# ProPrj___2026-03-26.net
KiCad netlist of a schematic drawn in EasyEDA Pro
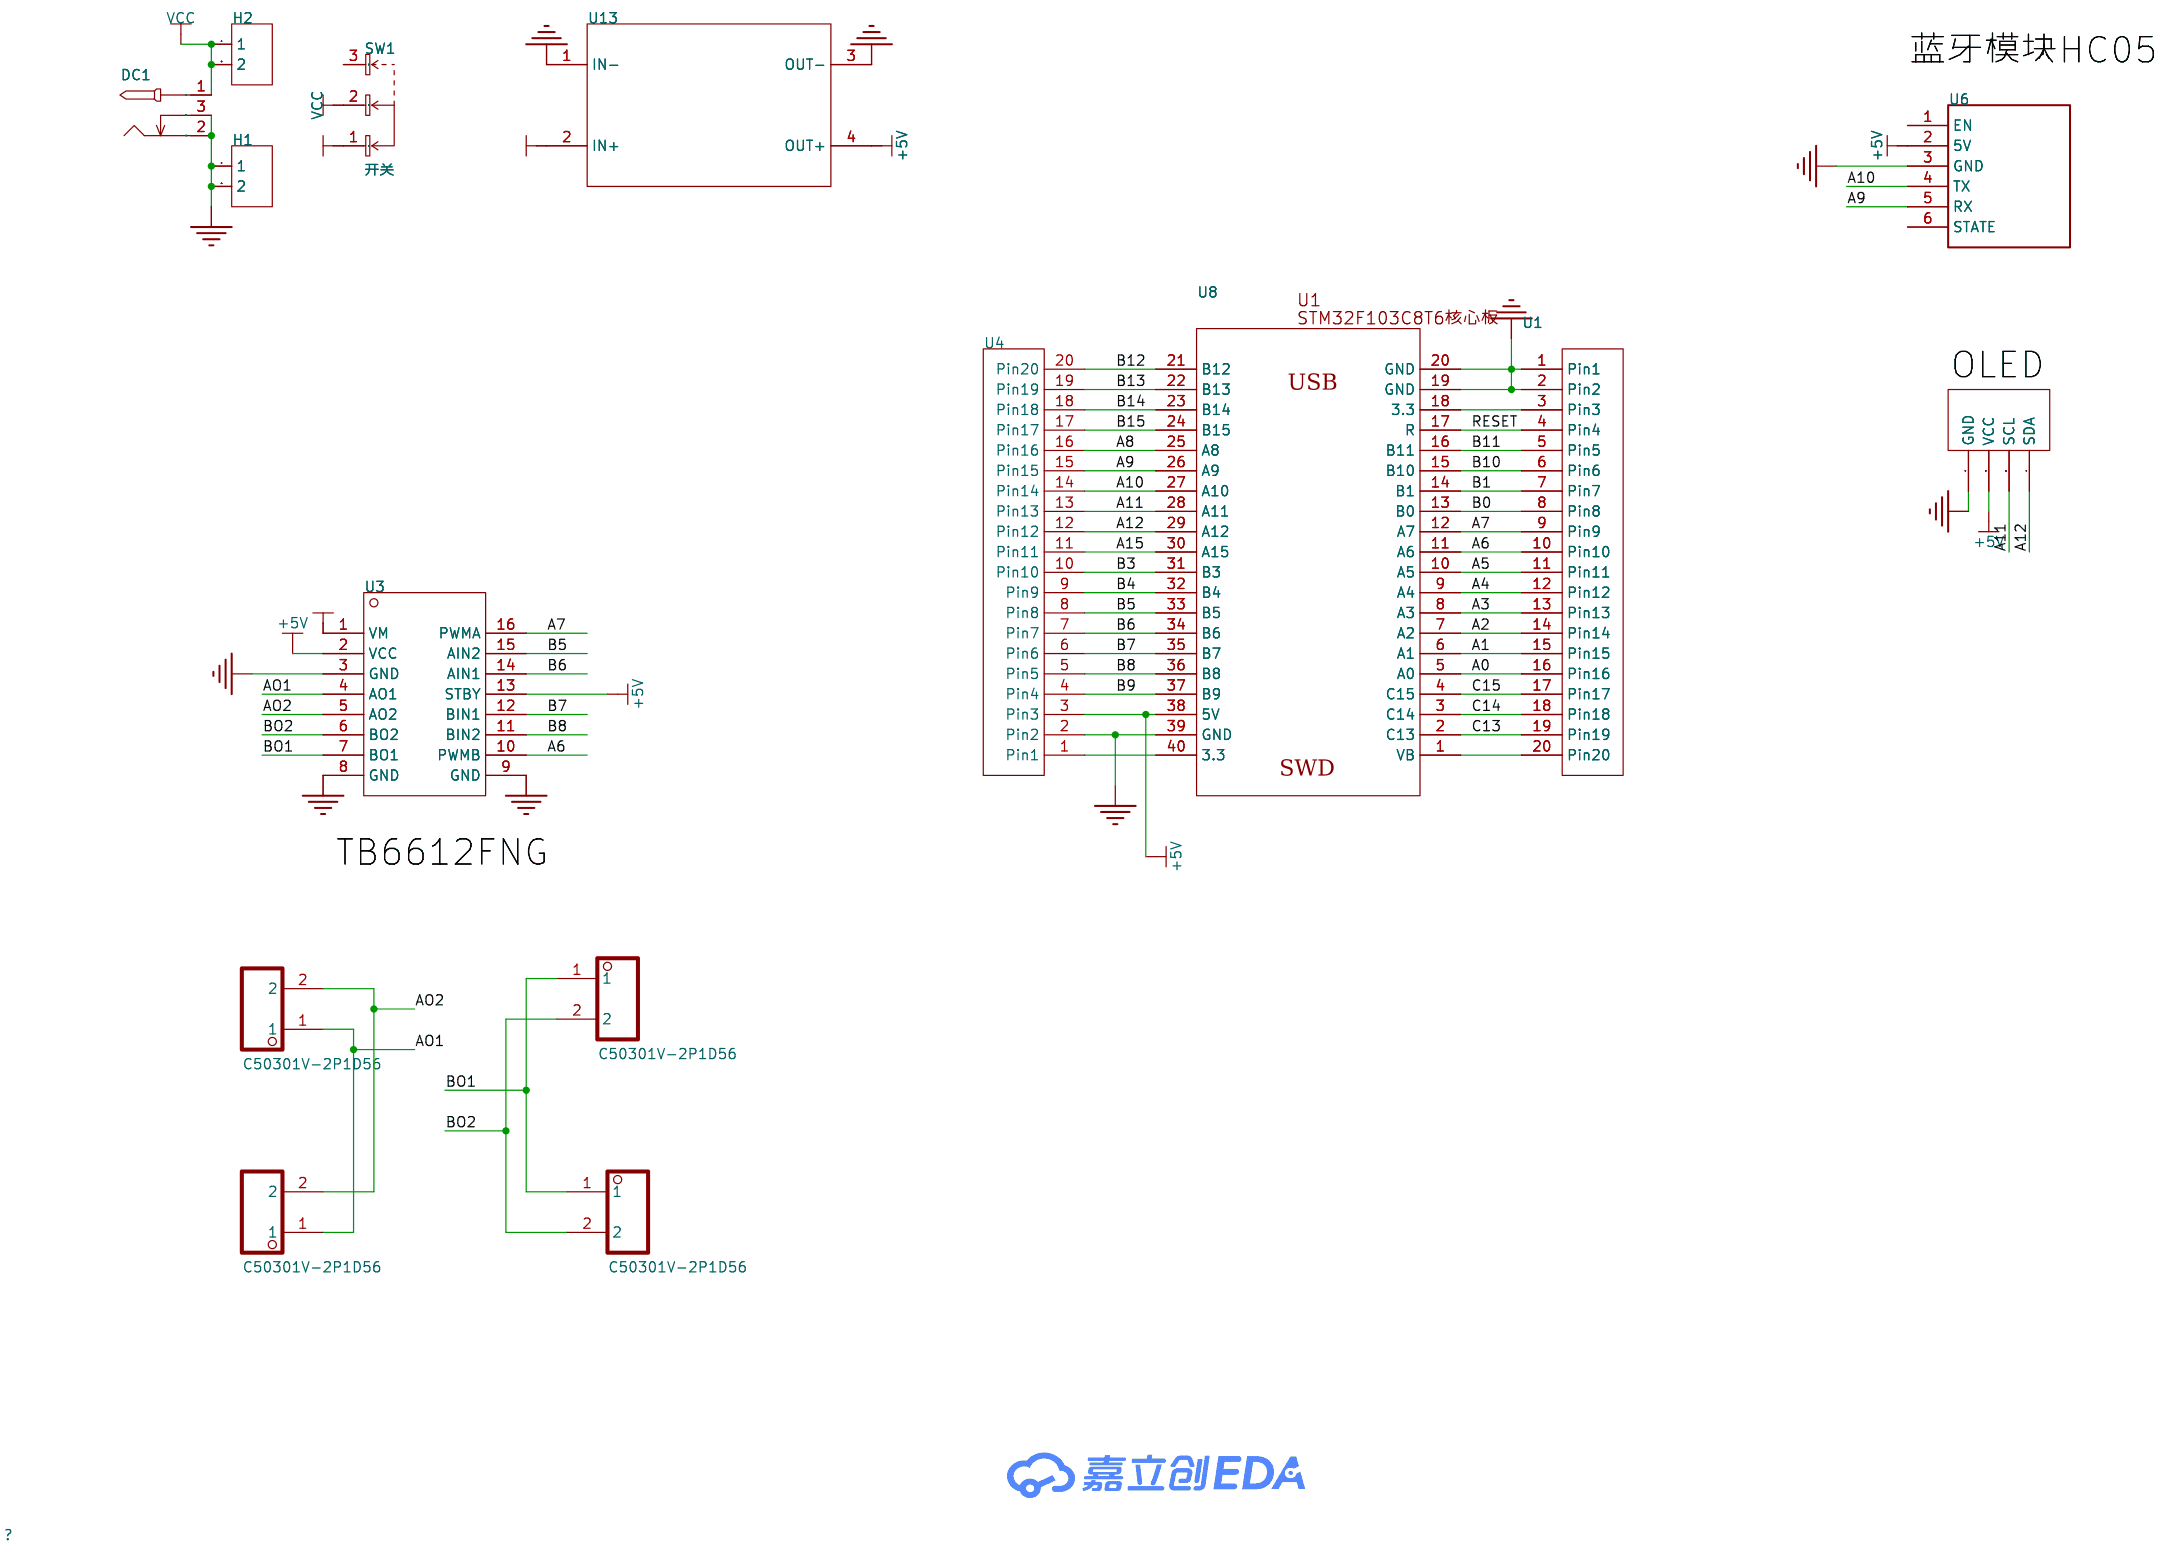
[diagram p0: schematic sheet]

(export (version "E")
  (design (tool "Eeschema 10.0.6"))
  (components
    (comp (ref "DC1")
      (value "~")
      (footprint "easyedapro:DC-005_2.5")
      (libsource (lib "easyedapro") (part "DC-005_2.5"))
    )
    (comp (ref "H1")
      (value "~")
      (footprint "easyedapro:HDR-TH_2P-P2.54-V-F")
      (libsource (lib "easyedapro") (part "Header-Female-2.54_1x2"))
    )
    (comp (ref "H2")
      (value "~")
      (footprint "easyedapro:HDR-TH_2P-P2.54-V-F")
      (libsource (lib "easyedapro") (part "Header-Female-2.54_1x2"))
    )
    (comp (ref "OLED")
      (value "OLED4PIN")
      (footprint "easyedapro:OLED 4PIN")
      (libsource (lib "easyedapro") (part "OLED 4PIN"))
    )
    (comp (ref "SW1")
      (value "开关")
      (footprint "easyedapro:SW-TH_3P-P4.70_L11.1-W12.7")
      (description "电路结构:单刀双掷;安装方式:-;开关颜色:黑色;额定电流:3A;额定电压:250V;工作寿命:1万次;")
      (fields
        (field (name "Manufacturer Part") "SS-12D06L5")
        (field (name "Manufacturer") "XKB Connection(中国星坤)")
      )
      (libsource (lib "easyedapro") (part "SS-12D06L5"))
    )
    (comp (ref "U1") (value "~") (footprint "easyedapro:20p排针") (libsource (lib "easyedapro") (part "20p排针")))
    (comp (ref "U3")
      (value "TB6612FNG")
      (footprint "easyedapro:TB6612")
      (libsource (lib "easyedapro") (part "TB6612"))
    )
    (comp (ref "U4") (value "~") (footprint "easyedapro:20p排针") (libsource (lib "easyedapro") (part "20p排针")))
    (comp (ref "U6")
      (value "蓝牙模块HC05")
      (footprint "easyedapro:HC05")
      (libsource (lib "easyedapro") (part "HC05"))
    )
    (comp (ref "U8")
      (value "~")
      (footprint "easyedapro:STM32F103C8T6核心板")
      (libsource (lib "easyedapro") (part "STM32F103核心板"))
    )
    (comp (ref "U9")
      (value "C50301V-2P1D56")
      (footprint "easyedapro:螺钉式接线端子")
      (description "低价方案")
      (libsource (lib "easyedapro") (part "螺钉式接线端子"))
    )
    (comp (ref "U10")
      (value "C50301V-2P1D56")
      (footprint "easyedapro:螺钉式接线端子")
      (description "低价方案")
      (libsource (lib "easyedapro") (part "螺钉式接线端子"))
    )
    (comp (ref "U11")
      (value "C50301V-2P1D56")
      (footprint "easyedapro:螺钉式接线端子")
      (description "低价方案")
      (libsource (lib "easyedapro") (part "螺钉式接线端子"))
    )
    (comp (ref "U12")
      (value "C50301V-2P1D56")
      (footprint "easyedapro:螺钉式接线端子")
      (description "低价方案")
      (libsource (lib "easyedapro") (part "螺钉式接线端子"))
    )
    (comp (ref "U13")
      (value "~")
      (footprint "easyedapro:MP1584en")
      (libsource (lib "easyedapro") (part "MP1584en"))
    )
  )
  (nets
    (net (code "1") (name "+5V") (class "Default")
      (node (ref "OLED") (pin "2") (pinfunction "VCC_2") (pintype "input"))
      (node (ref "U13") (pin "4") (pinfunction "OUT+_4") (pintype "input"))
      (node (ref "U3") (pin "13") (pinfunction "STBY_13") (pintype "input"))
      (node (ref "U3") (pin "2") (pinfunction "VCC_2") (pintype "input"))
      (node (ref "U4") (pin "3") (pinfunction "Pin3_3") (pintype "input"))
      (node (ref "U6") (pin "2") (pinfunction "5V_2") (pintype "unspecified"))
      (node (ref "U8") (pin "38") (pinfunction "5V_38") (pintype "input"))
    )
    (net (code "2") (name "+12V") (class "Default")
      (node (ref "SW1") (pin "1") (pinfunction "1_1") (pintype "unspecified"))
      (node (ref "U13") (pin "2") (pinfunction "IN+_2") (pintype "input"))
      (node (ref "U3") (pin "1") (pinfunction "VM_1") (pintype "input"))
    )
    (net (code "3") (name "/A0") (class "Default")
      (node (ref "U1") (pin "16") (pinfunction "Pin16_16") (pintype "input"))
      (node (ref "U8") (pin "5") (pinfunction "A0_5") (pintype "input"))
    )
    (net (code "4") (name "/A1") (class "Default")
      (node (ref "U1") (pin "15") (pinfunction "Pin15_15") (pintype "input"))
      (node (ref "U8") (pin "6") (pinfunction "A1_6") (pintype "input"))
    )
    (net (code "5") (name "/A2") (class "Default")
      (node (ref "U1") (pin "14") (pinfunction "Pin14_14") (pintype "input"))
      (node (ref "U8") (pin "7") (pinfunction "A2_7") (pintype "input"))
    )
    (net (code "6") (name "/A3") (class "Default")
      (node (ref "U1") (pin "13") (pinfunction "Pin13_13") (pintype "input"))
      (node (ref "U8") (pin "8") (pinfunction "A3_8") (pintype "input"))
    )
    (net (code "7") (name "/A4") (class "Default")
      (node (ref "U1") (pin "12") (pinfunction "Pin12_12") (pintype "input"))
      (node (ref "U8") (pin "9") (pinfunction "A4_9") (pintype "input"))
    )
    (net (code "8") (name "/A5") (class "Default")
      (node (ref "U1") (pin "11") (pinfunction "Pin11_11") (pintype "input"))
      (node (ref "U8") (pin "10") (pinfunction "A5_10") (pintype "input"))
    )
    (net (code "9") (name "/A6") (class "Default")
      (node (ref "U1") (pin "10") (pinfunction "Pin10_10") (pintype "input"))
      (node (ref "U3") (pin "10") (pinfunction "PWMB_10") (pintype "input"))
      (node (ref "U8") (pin "11") (pinfunction "A6_11") (pintype "input"))
    )
    (net (code "10") (name "/A7") (class "Default")
      (node (ref "U1") (pin "9") (pinfunction "Pin9_9") (pintype "input"))
      (node (ref "U3") (pin "16") (pinfunction "PWMA_16") (pintype "input"))
      (node (ref "U8") (pin "12") (pinfunction "A7_12") (pintype "input"))
    )
    (net (code "11") (name "/A8") (class "Default")
      (node (ref "U4") (pin "16") (pinfunction "Pin16_16") (pintype "input"))
      (node (ref "U8") (pin "25") (pinfunction "A8_25") (pintype "input"))
    )
    (net (code "12") (name "/A9") (class "Default")
      (node (ref "U4") (pin "15") (pinfunction "Pin15_15") (pintype "input"))
      (node (ref "U6") (pin "5") (pinfunction "RX_5") (pintype "unspecified"))
      (node (ref "U8") (pin "26") (pinfunction "A9_26") (pintype "input"))
    )
    (net (code "13") (name "/A10") (class "Default")
      (node (ref "U4") (pin "14") (pinfunction "Pin14_14") (pintype "input"))
      (node (ref "U6") (pin "4") (pinfunction "TX_4") (pintype "unspecified"))
      (node (ref "U8") (pin "27") (pinfunction "A10_27") (pintype "input"))
    )
    (net (code "14") (name "/A11") (class "Default")
      (node (ref "OLED") (pin "3") (pinfunction "SCL_3") (pintype "input"))
      (node (ref "U4") (pin "13") (pinfunction "Pin13_13") (pintype "input"))
      (node (ref "U8") (pin "28") (pinfunction "A11_28") (pintype "input"))
    )
    (net (code "15") (name "/A12") (class "Default")
      (node (ref "OLED") (pin "4") (pinfunction "SDA_4") (pintype "input"))
      (node (ref "U4") (pin "12") (pinfunction "Pin12_12") (pintype "input"))
      (node (ref "U8") (pin "29") (pinfunction "A12_29") (pintype "input"))
    )
    (net (code "16") (name "/A15") (class "Default")
      (node (ref "U4") (pin "11") (pinfunction "Pin11_11") (pintype "input"))
      (node (ref "U8") (pin "30") (pinfunction "A15_30") (pintype "input"))
    )
    (net (code "17") (name "/AO1") (class "Default")
      (node (ref "U10") (pin "1") (pinfunction "1_1") (pintype "bidirectional"))
      (node (ref "U3") (pin "4") (pinfunction "AO1_4") (pintype "input"))
      (node (ref "U9") (pin "1") (pinfunction "1_1") (pintype "bidirectional"))
    )
    (net (code "18") (name "/AO2") (class "Default")
      (node (ref "U10") (pin "2") (pinfunction "2_2") (pintype "bidirectional"))
      (node (ref "U3") (pin "5") (pinfunction "AO2_5") (pintype "input"))
      (node (ref "U9") (pin "2") (pinfunction "2_2") (pintype "bidirectional"))
    )
    (net (code "19") (name "/B0") (class "Default")
      (node (ref "U1") (pin "8") (pinfunction "Pin8_8") (pintype "input"))
      (node (ref "U8") (pin "13") (pinfunction "B0_13") (pintype "input"))
    )
    (net (code "20") (name "/B1") (class "Default")
      (node (ref "U1") (pin "7") (pinfunction "Pin7_7") (pintype "input"))
      (node (ref "U8") (pin "14") (pinfunction "B1_14") (pintype "input"))
    )
    (net (code "21") (name "/B3") (class "Default")
      (node (ref "U4") (pin "10") (pinfunction "Pin10_10") (pintype "input"))
      (node (ref "U8") (pin "31") (pinfunction "B3_31") (pintype "input"))
    )
    (net (code "22") (name "/B4") (class "Default")
      (node (ref "U4") (pin "9") (pinfunction "Pin9_9") (pintype "input"))
      (node (ref "U8") (pin "32") (pinfunction "B4_32") (pintype "input"))
    )
    (net (code "23") (name "/B5") (class "Default")
      (node (ref "U3") (pin "15") (pinfunction "AIN2_15") (pintype "input"))
      (node (ref "U4") (pin "8") (pinfunction "Pin8_8") (pintype "input"))
      (node (ref "U8") (pin "33") (pinfunction "B5_33") (pintype "input"))
    )
    (net (code "24") (name "/B6") (class "Default")
      (node (ref "U3") (pin "14") (pinfunction "AIN1_14") (pintype "input"))
      (node (ref "U4") (pin "7") (pinfunction "Pin7_7") (pintype "input"))
      (node (ref "U8") (pin "34") (pinfunction "B6_34") (pintype "input"))
    )
    (net (code "25") (name "/B7") (class "Default")
      (node (ref "U3") (pin "12") (pinfunction "BIN1_12") (pintype "input"))
      (node (ref "U4") (pin "6") (pinfunction "Pin6_6") (pintype "input"))
      (node (ref "U8") (pin "35") (pinfunction "B7_35") (pintype "input"))
    )
    (net (code "26") (name "/B8") (class "Default")
      (node (ref "U3") (pin "11") (pinfunction "BIN2_11") (pintype "input"))
      (node (ref "U4") (pin "5") (pinfunction "Pin5_5") (pintype "input"))
      (node (ref "U8") (pin "36") (pinfunction "B8_36") (pintype "input"))
    )
    (net (code "27") (name "/B9") (class "Default")
      (node (ref "U4") (pin "4") (pinfunction "Pin4_4") (pintype "input"))
      (node (ref "U8") (pin "37") (pinfunction "B9_37") (pintype "input"))
    )
    (net (code "28") (name "/B10") (class "Default")
      (node (ref "U1") (pin "6") (pinfunction "Pin6_6") (pintype "input"))
      (node (ref "U8") (pin "15") (pinfunction "B10_15") (pintype "input"))
    )
    (net (code "29") (name "/B11") (class "Default")
      (node (ref "U1") (pin "5") (pinfunction "Pin5_5") (pintype "input"))
      (node (ref "U8") (pin "16") (pinfunction "B11_16") (pintype "input"))
    )
    (net (code "30") (name "/B12") (class "Default")
      (node (ref "U4") (pin "20") (pinfunction "Pin20_20") (pintype "input"))
      (node (ref "U8") (pin "21") (pinfunction "B12_21") (pintype "input"))
    )
    (net (code "31") (name "/B13") (class "Default")
      (node (ref "U4") (pin "19") (pinfunction "Pin19_19") (pintype "input"))
      (node (ref "U8") (pin "22") (pinfunction "B13_22") (pintype "input"))
    )
    (net (code "32") (name "/B14") (class "Default")
      (node (ref "U4") (pin "18") (pinfunction "Pin18_18") (pintype "input"))
      (node (ref "U8") (pin "23") (pinfunction "B14_23") (pintype "input"))
    )
    (net (code "33") (name "/B15") (class "Default")
      (node (ref "U4") (pin "17") (pinfunction "Pin17_17") (pintype "input"))
      (node (ref "U8") (pin "24") (pinfunction "B15_24") (pintype "input"))
    )
    (net (code "34") (name "/BO1") (class "Default")
      (node (ref "U11") (pin "1") (pinfunction "1_1") (pintype "bidirectional"))
      (node (ref "U12") (pin "1") (pinfunction "1_1") (pintype "bidirectional"))
      (node (ref "U3") (pin "7") (pinfunction "BO1_7") (pintype "input"))
    )
    (net (code "35") (name "/BO2") (class "Default")
      (node (ref "U11") (pin "2") (pinfunction "2_2") (pintype "bidirectional"))
      (node (ref "U12") (pin "2") (pinfunction "2_2") (pintype "bidirectional"))
      (node (ref "U3") (pin "6") (pinfunction "BO2_6") (pintype "input"))
    )
    (net (code "36") (name "/C13") (class "Default")
      (node (ref "U1") (pin "19") (pinfunction "Pin19_19") (pintype "input"))
      (node (ref "U8") (pin "2") (pinfunction "C13_2") (pintype "input"))
    )
    (net (code "37") (name "/C14") (class "Default")
      (node (ref "U1") (pin "18") (pinfunction "Pin18_18") (pintype "input"))
      (node (ref "U8") (pin "3") (pinfunction "C14_3") (pintype "input"))
    )
    (net (code "38") (name "/C15") (class "Default")
      (node (ref "U1") (pin "17") (pinfunction "Pin17_17") (pintype "input"))
      (node (ref "U8") (pin "4") (pinfunction "C15_4") (pintype "input"))
    )
    (net (code "39") (name "/RESET") (class "Default")
      (node (ref "U1") (pin "4") (pinfunction "Pin4_4") (pintype "input"))
      (node (ref "U8") (pin "17") (pinfunction "R_17") (pintype "input"))
    )
    (net (code "40") (name "GND") (class "Default")
      (node (ref "DC1") (pin "2") (pinfunction "2_2") (pintype "input"))
      (node (ref "DC1") (pin "3") (pinfunction "3_3") (pintype "input"))
      (node (ref "H1") (pin "1") (pinfunction "1_1") (pintype "input"))
      (node (ref "H1") (pin "2") (pinfunction "2_2") (pintype "input"))
      (node (ref "OLED") (pin "1") (pinfunction "GND_1") (pintype "input"))
      (node (ref "U1") (pin "1") (pinfunction "Pin1_1") (pintype "input"))
      (node (ref "U1") (pin "2") (pinfunction "Pin2_2") (pintype "input"))
      (node (ref "U13") (pin "1") (pinfunction "IN-_1") (pintype "input"))
      (node (ref "U13") (pin "3") (pinfunction "OUT-_3") (pintype "input"))
      (node (ref "U3") (pin "3") (pinfunction "GND_3") (pintype "input"))
      (node (ref "U3") (pin "8") (pinfunction "GND_8") (pintype "input"))
      (node (ref "U3") (pin "9") (pinfunction "GND_9") (pintype "input"))
      (node (ref "U4") (pin "2") (pinfunction "Pin2_2") (pintype "input"))
      (node (ref "U6") (pin "3") (pinfunction "GND_3") (pintype "unspecified"))
      (node (ref "U8") (pin "19") (pinfunction "GND_19") (pintype "input"))
      (node (ref "U8") (pin "20") (pinfunction "GND_20") (pintype "input"))
      (node (ref "U8") (pin "39") (pinfunction "GND_39") (pintype "input"))
    )
    (net (code "41") (name "Net-(U1-Pin3)") (class "Default")
      (node (ref "U1") (pin "3") (pinfunction "Pin3_3") (pintype "input"))
      (node (ref "U8") (pin "18") (pinfunction "3.3_18") (pintype "input"))
    )
    (net (code "42") (name "Net-(U1-Pin20)") (class "Default")
      (node (ref "U1") (pin "20") (pinfunction "Pin20_20") (pintype "input"))
      (node (ref "U8") (pin "1") (pinfunction "VB_1") (pintype "input"))
    )
    (net (code "43") (name "Net-(U4-Pin1)") (class "Default")
      (node (ref "U4") (pin "1") (pinfunction "Pin1_1") (pintype "input"))
      (node (ref "U8") (pin "40") (pinfunction "3.3_40") (pintype "input"))
    )
    (net (code "44") (name "VCC") (class "Default")
      (node (ref "DC1") (pin "1") (pinfunction "4_1") (pintype "input"))
      (node (ref "H2") (pin "1") (pinfunction "1_1") (pintype "input"))
      (node (ref "H2") (pin "2") (pinfunction "2_2") (pintype "input"))
      (node (ref "SW1") (pin "2") (pinfunction "2_2") (pintype "unspecified"))
    )
    (net (code "45") (name "unconnected-(SW1-Pad3)") (class "Default")
      (node (ref "SW1") (pin "3") (pinfunction "3_3") (pintype "unspecified"))
    )
    (net (code "46") (name "unconnected-(U6-EN-Pad1)") (class "Default")
      (node (ref "U6") (pin "1") (pinfunction "EN_1") (pintype "unspecified"))
    )
    (net (code "47") (name "unconnected-(U6-STATE-Pad6)") (class "Default")
      (node (ref "U6") (pin "6") (pinfunction "STATE_6") (pintype "unspecified"))
    )
  )
)
